# PCB_TopSchematic.net
KiCad netlist of a schematic drawn in Altium Designer
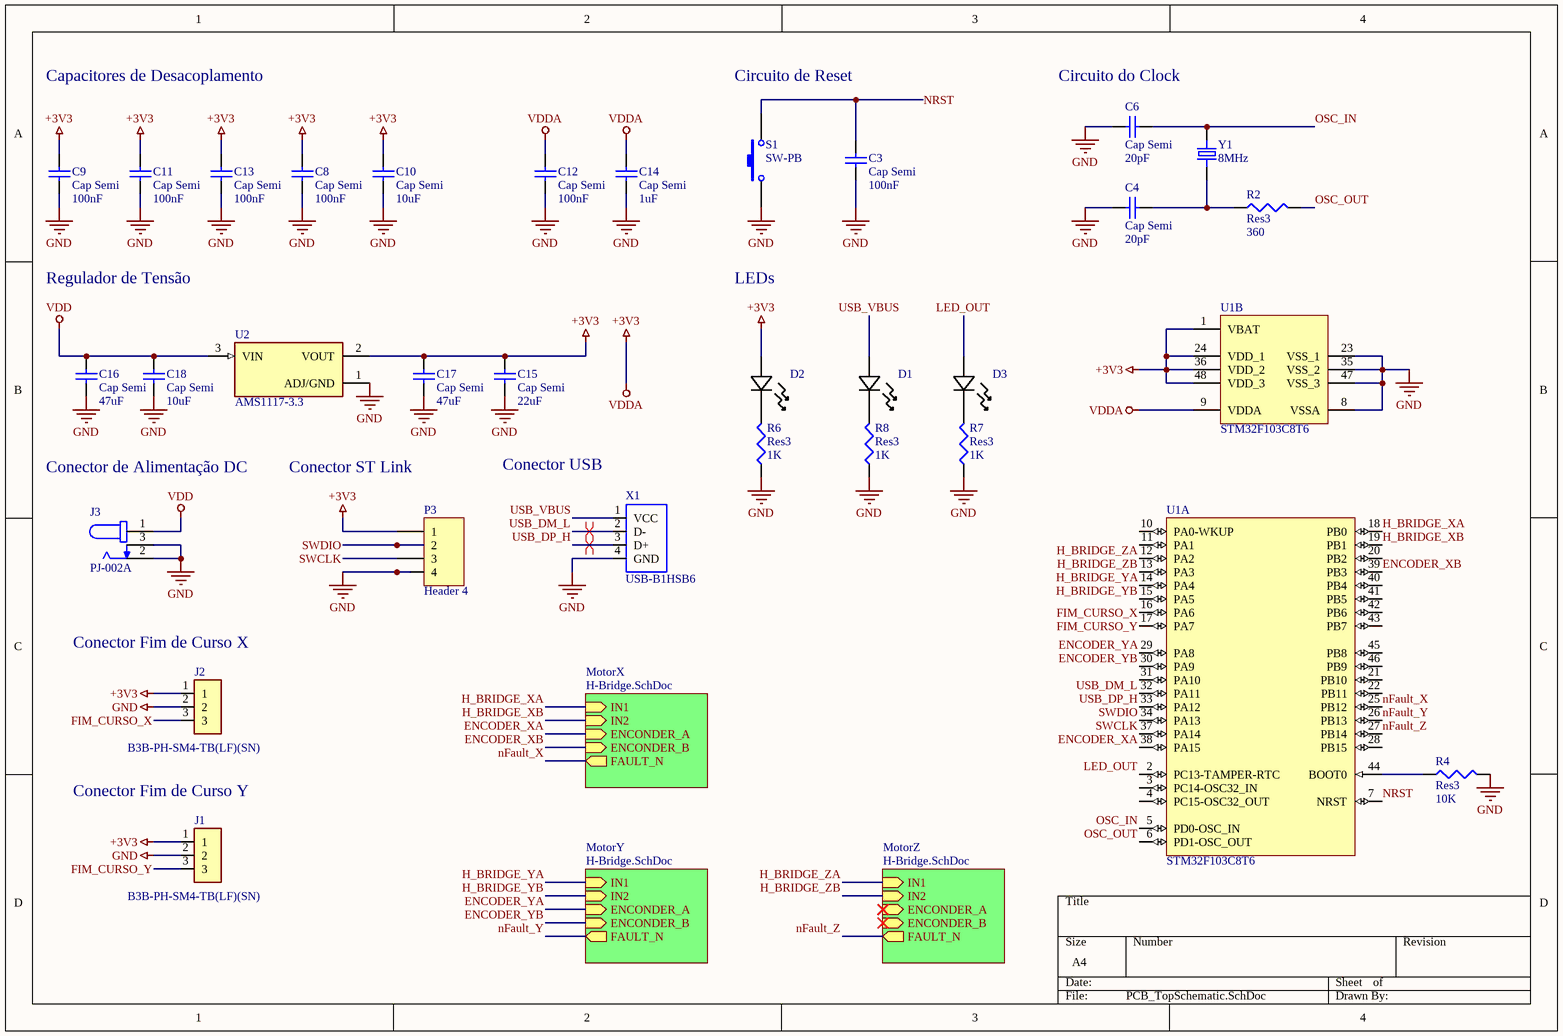
[diagram p0: PCB_TopSchematic.SchDoc]

(export (version "E")
  (design (tool "Eeschema 10.0.6"))
  (components
    (comp (ref "C3")
      (value "Cap Semi")
      (footprint "1608[0603]")
      (description "Capacitor (Semiconductor SIM Model)")
      (fields (field (name "ALTIUM_VALUE") "100nF") (field (name "PUBLISHER") "Altium Limited"))
      (libsource (lib "Miscellaneous Devices") (part "Cap Semi"))
    )
    (comp (ref "C4")
      (value "Cap Semi")
      (footprint "1608[0603]")
      (description "Capacitor (Semiconductor SIM Model)")
      (fields (field (name "ALTIUM_VALUE") "20pF") (field (name "PUBLISHER") "Altium Limited"))
      (libsource (lib "Miscellaneous Devices") (part "Cap Semi"))
    )
    (comp (ref "C6")
      (value "Cap Semi")
      (footprint "1608[0603]")
      (description "Capacitor (Semiconductor SIM Model)")
      (fields (field (name "ALTIUM_VALUE") "20pF") (field (name "PUBLISHER") "Altium Limited"))
      (libsource (lib "Miscellaneous Devices") (part "Cap Semi"))
    )
    (comp (ref "C8")
      (value "Cap Semi")
      (footprint "1608[0603]")
      (description "Capacitor (Semiconductor SIM Model)")
      (fields (field (name "ALTIUM_VALUE") "100nF") (field (name "PUBLISHER") "Altium Limited"))
      (libsource (lib "Miscellaneous Devices") (part "Cap Semi"))
    )
    (comp (ref "C9")
      (value "Cap Semi")
      (footprint "1608[0603]")
      (description "Capacitor (Semiconductor SIM Model)")
      (fields (field (name "ALTIUM_VALUE") "100nF") (field (name "PUBLISHER") "Altium Limited"))
      (libsource (lib "Miscellaneous Devices") (part "Cap Semi"))
    )
    (comp (ref "C10")
      (value "Cap Semi")
      (footprint "1608[0603]")
      (description "Capacitor (Semiconductor SIM Model)")
      (fields (field (name "ALTIUM_VALUE") "10uF") (field (name "PUBLISHER") "Altium Limited"))
      (libsource (lib "Miscellaneous Devices") (part "Cap Semi"))
    )
    (comp (ref "C11")
      (value "Cap Semi")
      (footprint "1608[0603]")
      (description "Capacitor (Semiconductor SIM Model)")
      (fields (field (name "ALTIUM_VALUE") "100nF") (field (name "PUBLISHER") "Altium Limited"))
      (libsource (lib "Miscellaneous Devices") (part "Cap Semi"))
    )
    (comp (ref "C12")
      (value "Cap Semi")
      (footprint "1608[0603]")
      (description "Capacitor (Semiconductor SIM Model)")
      (fields (field (name "ALTIUM_VALUE") "100nF") (field (name "PUBLISHER") "Altium Limited"))
      (libsource (lib "Miscellaneous Devices") (part "Cap Semi"))
    )
    (comp (ref "C13")
      (value "Cap Semi")
      (footprint "1608[0603]")
      (description "Capacitor (Semiconductor SIM Model)")
      (fields (field (name "ALTIUM_VALUE") "100nF") (field (name "PUBLISHER") "Altium Limited"))
      (libsource (lib "Miscellaneous Devices") (part "Cap Semi"))
    )
    (comp (ref "C14")
      (value "Cap Semi")
      (footprint "1608[0603]")
      (description "Capacitor (Semiconductor SIM Model)")
      (fields (field (name "ALTIUM_VALUE") "1uF") (field (name "PUBLISHER") "Altium Limited"))
      (libsource (lib "Miscellaneous Devices") (part "Cap Semi"))
    )
    (comp (ref "C15")
      (value "Cap Semi")
      (footprint "1608[0603]")
      (description "Capacitor (Semiconductor SIM Model)")
      (fields (field (name "ALTIUM_VALUE") "22uF") (field (name "PUBLISHER") "Altium Limited"))
      (libsource (lib "Miscellaneous Devices") (part "Cap Semi"))
    )
    (comp (ref "C16")
      (value "Cap Semi")
      (footprint "1608[0603]")
      (description "Capacitor (Semiconductor SIM Model)")
      (fields (field (name "ALTIUM_VALUE") "47uF") (field (name "PUBLISHER") "Altium Limited"))
      (libsource (lib "Miscellaneous Devices") (part "Cap Semi"))
    )
    (comp (ref "C17")
      (value "Cap Semi")
      (footprint "1608[0603]")
      (description "Capacitor (Semiconductor SIM Model)")
      (fields (field (name "ALTIUM_VALUE") "47uF") (field (name "PUBLISHER") "Altium Limited"))
      (libsource (lib "Miscellaneous Devices") (part "Cap Semi"))
    )
    (comp (ref "C18")
      (value "Cap Semi")
      (footprint "1608[0603]")
      (description "Capacitor (Semiconductor SIM Model)")
      (fields (field (name "ALTIUM_VALUE") "10uF") (field (name "PUBLISHER") "Altium Limited"))
      (libsource (lib "Miscellaneous Devices") (part "Cap Semi"))
    )
    (comp (ref "D1")
      (value "SML-E12M8WT86")
      (footprint "LED_SMLD12_ROM")
      (description "No Description Available")
      (fields (field (name "COPYRIGHT") "Copyright (C) 2018 Accelerated Designs. All rights reserved"))
      (libsource (lib "2020-07-03_21-25-34") (part "SML-E12M8WT86"))
    )
    (comp (ref "D2")
      (value "SML-E12M8WT86")
      (footprint "LED_SMLD12_ROM")
      (description "No Description Available")
      (fields (field (name "COPYRIGHT") "Copyright (C) 2018 Accelerated Designs. All rights reserved"))
      (libsource (lib "2020-07-03_21-25-34") (part "SML-E12M8WT86"))
    )
    (comp (ref "D3")
      (value "SML-E12M8WT86")
      (footprint "LED_SMLD12_ROM")
      (description "No Description Available")
      (fields (field (name "COPYRIGHT") "Copyright (C) 2018 Accelerated Designs. All rights reserved"))
      (libsource (lib "2020-07-03_21-25-34") (part "SML-E12M8WT86"))
    )
    (comp (ref "J1")
      (value "B3B-PH-SM4-TB(LF)(SN)")
      (footprint "JST_B3B-PH-SM4-TB(LF)(SN)")
      (description "Connector Header Surface Mount 3 position 0.079 _2.00mm_")
      (fields (field (name "MF") "JST Sales") (field (name "DIGI-KEY_PART_NUMBER") "455-1735-1-ND"))
      (libsource (lib "B3B-PH-SM4-TB_LF__SN_") (part "B3B-PH-SM4-TB(LF)(SN)"))
    )
    (comp (ref "J2")
      (value "B3B-PH-SM4-TB(LF)(SN)")
      (footprint "JST_B3B-PH-SM4-TB(LF)(SN)")
      (description "Connector Header Surface Mount 3 position 0.079 _2.00mm_")
      (fields (field (name "MF") "JST Sales") (field (name "DIGI-KEY_PART_NUMBER") "455-1735-1-ND"))
      (libsource (lib "B3B-PH-SM4-TB_LF__SN_") (part "B3B-PH-SM4-TB(LF)(SN)"))
    )
    (comp (ref "J3")
      (value "PJ-002A")
      (footprint "CUI_PJ-002A")
      (description "2,0 x 6,5 mm, 2,5 A, Yatay, A莽谋k Delik, Dc G眉莽 Jak谋 Konnekt枚r眉")
      (fields (field (name "MF") "CUI Devices"))
      (libsource (lib "PJ-002A") (part "PJ-002A"))
    )
    (comp (ref "P3")
      (value "Header 4")
      (footprint "HDR1X4")
      (description "Header, 4-Pin")
      (fields (field (name "PUBLISHER") "Altium Limited"))
      (libsource (lib "Miscellaneous Connectors") (part "Header 4"))
    )
    (comp (ref "R2")
      (value "Res3")
      (footprint "RESC1607X60N")
      (description "Resistor")
      (fields (field (name "ALTIUM_VALUE") "360") (field (name "PUBLISHER") "Altium Limited"))
      (libsource (lib "Miscellaneous Devices") (part "Res3"))
    )
    (comp (ref "R4")
      (value "Res3")
      (footprint "RESC1607X60N")
      (description "Resistor")
      (fields (field (name "ALTIUM_VALUE") "10K") (field (name "PUBLISHER") "Altium Limited"))
      (libsource (lib "Miscellaneous Devices") (part "Res3"))
    )
    (comp (ref "R6")
      (value "Res3")
      (footprint "RESC1607X60N")
      (description "Resistor")
      (fields (field (name "ALTIUM_VALUE") "1K") (field (name "PUBLISHER") "Altium Limited"))
      (libsource (lib "Miscellaneous Devices") (part "Res3"))
    )
    (comp (ref "R7")
      (value "Res3")
      (footprint "RESC1607X60N")
      (description "Resistor")
      (fields (field (name "ALTIUM_VALUE") "1K") (field (name "PUBLISHER") "Altium Limited"))
      (libsource (lib "Miscellaneous Devices") (part "Res3"))
    )
    (comp (ref "R8")
      (value "Res3")
      (footprint "RESC1607X60N")
      (description "Resistor")
      (fields (field (name "ALTIUM_VALUE") "1K") (field (name "PUBLISHER") "Altium Limited"))
      (libsource (lib "Miscellaneous Devices") (part "Res3"))
    )
    (comp (ref "S1")
      (value "SW-PB")
      (footprint "SW_B3FS-1010P")
      (description "Switch")
      (fields (field (name "PUBLISHER") "Altium Limited"))
      (libsource (lib "Miscellaneous Devices") (part "SW-PB"))
    )
    (comp (ref "U1")
      (value "STM32F103C8T6")
      (footprint "STM-LQFP48_N")
      (libsource (lib "STMicroelectronics STM32 F1") (part "STM32F103C8T6"))
    )
    (comp (ref "U2")
      (value "AMS1117-3.3")
      (footprint "SOT229P700X180-4N")
      (description "Sot223/Pkg 1-Amp 3.3-Volt Low Drop Out Voltage Regulatator")
      (fields (field (name "MF") "Advanced Monolithic Systems"))
      (libsource (lib "AMS1117-3.3") (part "AMS1117-3.3"))
    )
    (comp (ref "X1")
      (value "USB-B1HSB6")
      (footprint "OST_USB-B1HSB6")
      (description "USB-B _USB TYPE-B_ Receptacle Connector 4 Position Through Hole, Right Angle")
      (fields (field (name "DIGI-KEY_PART_NUMBER") "ED2983-ND") (field (name "MF") "On Shore"))
      (libsource (lib "USB-B1HSB6") (part "USB-B1HSB6"))
    )
    (comp (ref "Y1")
      (value "8MHz")
      (footprint "XTAL_ECS-80-20-5PX-TR")
      (description "8MHz Â±30ppm Crystal 20pF 60 Ohms HC-49/US")
      (fields (field (name "MP") "ECS-80-20-5PX-TR") (field (name "DIGI-KEY_PART_NUMBER") "XC2076CT-ND"))
      (libsource (lib "ECS-80-20-5PX-TR") (part "ECS-80-20-5PX-TR"))
    )
  )
  (nets
    (net (code "1") (name "+3V3") (class "Default")
      (node (ref "C10") (pin "2") (pinfunction "2_2") (pintype "passive"))
      (node (ref "C11") (pin "2") (pinfunction "2_2") (pintype "passive"))
      (node (ref "C12") (pin "2") (pinfunction "2_2") (pintype "passive"))
      (node (ref "C13") (pin "2") (pinfunction "2_2") (pintype "passive"))
      (node (ref "C14") (pin "2") (pinfunction "2_2") (pintype "passive"))
      (node (ref "C15") (pin "2") (pinfunction "2_2") (pintype "passive"))
      (node (ref "C17") (pin "2") (pinfunction "2_2") (pintype "passive"))
      (node (ref "C8") (pin "2") (pinfunction "2_2") (pintype "passive"))
      (node (ref "C9") (pin "2") (pinfunction "2_2") (pintype "passive"))
      (node (ref "D2") (pin "2") (pinfunction "2_2") (pintype "passive"))
      (node (ref "J1") (pin "1") (pinfunction "1_1") (pintype "passive"))
      (node (ref "J2") (pin "1") (pinfunction "1_1") (pintype "passive"))
      (node (ref "P3") (pin "1") (pinfunction "1_1") (pintype "passive"))
      (node (ref "U1") (pin "1") (pinfunction "VBAT_1") (pintype "power_in"))
      (node (ref "U1") (pin "24") (pinfunction "VDD_1_24") (pintype "power_in"))
      (node (ref "U1") (pin "36") (pinfunction "VDD_2_36") (pintype "power_in"))
      (node (ref "U1") (pin "48") (pinfunction "VDD_3_48") (pintype "power_in"))
      (node (ref "U1") (pin "9") (pinfunction "VDDA_9") (pintype "power_in"))
      (node (ref "U2") (pin "2") (pinfunction "VOUT_2") (pintype "passive"))
    )
    (net (code "2") (name "/ENCODER_XA") (class "Default")
      (node (ref "U1") (pin "38") (pinfunction "PA15_38") (pintype "bidirectional"))
    )
    (net (code "3") (name "/ENCODER_XB") (class "Default")
      (node (ref "U1") (pin "39") (pinfunction "PB3_39") (pintype "bidirectional"))
    )
    (net (code "4") (name "/ENCODER_YA") (class "Default")
      (node (ref "U1") (pin "29") (pinfunction "PA8_29") (pintype "bidirectional"))
    )
    (net (code "5") (name "/ENCODER_YB") (class "Default")
      (node (ref "U1") (pin "30") (pinfunction "PA9_30") (pintype "bidirectional"))
    )
    (net (code "8") (name "/FIM_CURSO_X") (class "Default")
      (node (ref "J2") (pin "3") (pinfunction "3_3") (pintype "passive"))
      (node (ref "U1") (pin "16") (pinfunction "PA6_16") (pintype "bidirectional"))
    )
    (net (code "9") (name "/FIM_CURSO_Y") (class "Default")
      (node (ref "J1") (pin "3") (pinfunction "3_3") (pintype "passive"))
      (node (ref "U1") (pin "17") (pinfunction "PA7_17") (pintype "bidirectional"))
    )
    (net (code "10") (name "/H_BRIDGE_XA") (class "Default")
      (node (ref "U1") (pin "18") (pinfunction "PB0_18") (pintype "bidirectional"))
    )
    (net (code "11") (name "/H_BRIDGE_XB") (class "Default")
      (node (ref "U1") (pin "19") (pinfunction "PB1_19") (pintype "bidirectional"))
    )
    (net (code "12") (name "/H_BRIDGE_YA") (class "Default")
      (node (ref "U1") (pin "14") (pinfunction "PA4_14") (pintype "bidirectional"))
    )
    (net (code "13") (name "/H_BRIDGE_YB") (class "Default")
      (node (ref "U1") (pin "15") (pinfunction "PA5_15") (pintype "bidirectional"))
    )
    (net (code "14") (name "/H_BRIDGE_ZA") (class "Default")
      (node (ref "U1") (pin "12") (pinfunction "PA2_12") (pintype "bidirectional"))
    )
    (net (code "15") (name "/H_BRIDGE_ZB") (class "Default")
      (node (ref "U1") (pin "13") (pinfunction "PA3_13") (pintype "bidirectional"))
    )
    (net (code "16") (name "/LED_OUT") (class "Default")
      (node (ref "D3") (pin "2") (pinfunction "2_2") (pintype "passive"))
      (node (ref "U1") (pin "2") (pinfunction "PC13-TAMPER-RTC_2") (pintype "bidirectional"))
    )
    (net (code "17") (name "/NRST") (class "Default")
      (node (ref "C3") (pin "2") (pinfunction "2_2") (pintype "passive"))
      (node (ref "S1") (pin "2") (pinfunction "2_2") (pintype "passive"))
      (node (ref "U1") (pin "7") (pinfunction "NRST_7") (pintype "bidirectional"))
    )
    (net (code "18") (name "/OSC_IN") (class "Default")
      (node (ref "C6") (pin "1") (pinfunction "1_1") (pintype "passive"))
      (node (ref "U1") (pin "5") (pinfunction "PD0-OSC_IN_5") (pintype "bidirectional"))
      (node (ref "Y1") (pin "1") (pinfunction "1_1") (pintype "passive"))
    )
    (net (code "19") (name "/OSC_OUT") (class "Default")
      (node (ref "R2") (pin "2") (pinfunction "2_2") (pintype "passive"))
      (node (ref "U1") (pin "6") (pinfunction "PD1-OSC_OUT_6") (pintype "bidirectional"))
    )
    (net (code "20") (name "/SWCLK") (class "Default")
      (node (ref "P3") (pin "3") (pinfunction "3_3") (pintype "passive"))
      (node (ref "U1") (pin "37") (pinfunction "PA14_37") (pintype "bidirectional"))
    )
    (net (code "21") (name "/SWDIO") (class "Default")
      (node (ref "P3") (pin "2") (pinfunction "2_2") (pintype "passive"))
      (node (ref "U1") (pin "34") (pinfunction "PA13_34") (pintype "bidirectional"))
    )
    (net (code "22") (name "/USB_DM_L") (class "Default")
      (node (ref "U1") (pin "32") (pinfunction "PA11_32") (pintype "bidirectional"))
      (node (ref "X1") (pin "2") (pinfunction "D-_2") (pintype "bidirectional"))
    )
    (net (code "23") (name "/USB_DP_H") (class "Default")
      (node (ref "U1") (pin "33") (pinfunction "PA12_33") (pintype "bidirectional"))
      (node (ref "X1") (pin "3") (pinfunction "D+_3") (pintype "bidirectional"))
    )
    (net (code "24") (name "/USB_VBUS") (class "Default")
      (node (ref "D1") (pin "2") (pinfunction "2_2") (pintype "passive"))
      (node (ref "X1") (pin "1") (pinfunction "VCC_1") (pintype "power_in"))
    )
    (net (code "25") (name "/nFault_X") (class "Default")
      (node (ref "U1") (pin "25") (pinfunction "PB12_25") (pintype "bidirectional"))
    )
    (net (code "26") (name "/nFault_Y") (class "Default")
      (node (ref "U1") (pin "26") (pinfunction "PB13_26") (pintype "bidirectional"))
    )
    (net (code "27") (name "/nFault_Z") (class "Default")
      (node (ref "U1") (pin "27") (pinfunction "PB14_27") (pintype "bidirectional"))
    )
    (net (code "28") (name "GND") (class "Default")
      (node (ref "C10") (pin "1") (pinfunction "1_1") (pintype "passive"))
      (node (ref "C11") (pin "1") (pinfunction "1_1") (pintype "passive"))
      (node (ref "C12") (pin "1") (pinfunction "1_1") (pintype "passive"))
      (node (ref "C13") (pin "1") (pinfunction "1_1") (pintype "passive"))
      (node (ref "C14") (pin "1") (pinfunction "1_1") (pintype "passive"))
      (node (ref "C15") (pin "1") (pinfunction "1_1") (pintype "passive"))
      (node (ref "C16") (pin "1") (pinfunction "1_1") (pintype "passive"))
      (node (ref "C17") (pin "1") (pinfunction "1_1") (pintype "passive"))
      (node (ref "C18") (pin "1") (pinfunction "1_1") (pintype "passive"))
      (node (ref "C3") (pin "1") (pinfunction "1_1") (pintype "passive"))
      (node (ref "C4") (pin "2") (pinfunction "2_2") (pintype "passive"))
      (node (ref "C6") (pin "2") (pinfunction "2_2") (pintype "passive"))
      (node (ref "C8") (pin "1") (pinfunction "1_1") (pintype "passive"))
      (node (ref "C9") (pin "1") (pinfunction "1_1") (pintype "passive"))
      (node (ref "J1") (pin "2") (pinfunction "2_2") (pintype "passive"))
      (node (ref "J2") (pin "2") (pinfunction "2_2") (pintype "passive"))
      (node (ref "J3") (pin "2") (pinfunction "2_2") (pintype "passive"))
      (node (ref "J3") (pin "3") (pinfunction "3_3") (pintype "passive"))
      (node (ref "P3") (pin "4") (pinfunction "4_4") (pintype "passive"))
      (node (ref "R4") (pin "2") (pinfunction "2_2") (pintype "passive"))
      (node (ref "R6") (pin "1") (pinfunction "1_1") (pintype "passive"))
      (node (ref "R7") (pin "1") (pinfunction "1_1") (pintype "passive"))
      (node (ref "R8") (pin "1") (pinfunction "1_1") (pintype "passive"))
      (node (ref "S1") (pin "1") (pinfunction "1_1") (pintype "passive"))
      (node (ref "U1") (pin "23") (pinfunction "VSS_1_23") (pintype "power_in"))
      (node (ref "U1") (pin "35") (pinfunction "VSS_2_35") (pintype "power_in"))
      (node (ref "U1") (pin "47") (pinfunction "VSS_3_47") (pintype "power_in"))
      (node (ref "U1") (pin "8") (pinfunction "VSSA_8") (pintype "power_in"))
      (node (ref "U2") (pin "1") (pinfunction "ADJ/GND_1") (pintype "power_in"))
      (node (ref "X1") (pin "4") (pinfunction "GND_4") (pintype "power_in"))
    )
    (net (code "29") (name "Net-(C4-Pad1)") (class "Default")
      (node (ref "C4") (pin "1") (pinfunction "1_1") (pintype "passive"))
      (node (ref "R2") (pin "1") (pinfunction "1_1") (pintype "passive"))
      (node (ref "Y1") (pin "2") (pinfunction "2_2") (pintype "passive"))
    )
    (net (code "30") (name "Net-(D1-Pad1)") (class "Default")
      (node (ref "D1") (pin "1") (pinfunction "1_1") (pintype "passive"))
      (node (ref "R8") (pin "2") (pinfunction "2_2") (pintype "passive"))
    )
    (net (code "31") (name "Net-(D2-Pad1)") (class "Default")
      (node (ref "D2") (pin "1") (pinfunction "1_1") (pintype "passive"))
      (node (ref "R6") (pin "2") (pinfunction "2_2") (pintype "passive"))
    )
    (net (code "32") (name "Net-(D3-Pad1)") (class "Default")
      (node (ref "D3") (pin "1") (pinfunction "1_1") (pintype "passive"))
      (node (ref "R7") (pin "2") (pinfunction "2_2") (pintype "passive"))
    )
    (net (code "33") (name "Net-(U1A-BOOT0)") (class "Default")
      (node (ref "R4") (pin "1") (pinfunction "1_1") (pintype "passive"))
      (node (ref "U1") (pin "44") (pinfunction "BOOT0_44") (pintype "input"))
    )
    (net (code "34") (name "VDD") (class "Default")
      (node (ref "C16") (pin "2") (pinfunction "2_2") (pintype "passive"))
      (node (ref "C18") (pin "2") (pinfunction "2_2") (pintype "passive"))
      (node (ref "J3") (pin "1") (pinfunction "1_1") (pintype "passive"))
      (node (ref "U2") (pin "3") (pinfunction "VIN_3") (pintype "input"))
    )
    (net (code "35") (name "unconnected-(U1A-PA0-WKUP-Pad10)") (class "Default")
      (node (ref "U1") (pin "10") (pinfunction "PA0-WKUP_10") (pintype "bidirectional"))
    )
    (net (code "36") (name "unconnected-(U1A-PA1-Pad11)") (class "Default")
      (node (ref "U1") (pin "11") (pinfunction "PA1_11") (pintype "bidirectional"))
    )
    (net (code "37") (name "unconnected-(U1A-PA10-Pad31)") (class "Default")
      (node (ref "U1") (pin "31") (pinfunction "PA10_31") (pintype "bidirectional"))
    )
    (net (code "38") (name "unconnected-(U1A-PB2-Pad20)") (class "Default")
      (node (ref "U1") (pin "20") (pinfunction "PB2_20") (pintype "bidirectional"))
    )
    (net (code "39") (name "unconnected-(U1A-PB4-Pad40)") (class "Default")
      (node (ref "U1") (pin "40") (pinfunction "PB4_40") (pintype "bidirectional"))
    )
    (net (code "40") (name "unconnected-(U1A-PB5-Pad41)") (class "Default")
      (node (ref "U1") (pin "41") (pinfunction "PB5_41") (pintype "bidirectional"))
    )
    (net (code "41") (name "unconnected-(U1A-PB6-Pad42)") (class "Default")
      (node (ref "U1") (pin "42") (pinfunction "PB6_42") (pintype "bidirectional"))
    )
    (net (code "42") (name "unconnected-(U1A-PB7-Pad43)") (class "Default")
      (node (ref "U1") (pin "43") (pinfunction "PB7_43") (pintype "bidirectional"))
    )
    (net (code "43") (name "unconnected-(U1A-PB8-Pad45)") (class "Default")
      (node (ref "U1") (pin "45") (pinfunction "PB8_45") (pintype "bidirectional"))
    )
    (net (code "44") (name "unconnected-(U1A-PB9-Pad46)") (class "Default")
      (node (ref "U1") (pin "46") (pinfunction "PB9_46") (pintype "bidirectional"))
    )
    (net (code "45") (name "unconnected-(U1A-PB10-Pad21)") (class "Default")
      (node (ref "U1") (pin "21") (pinfunction "PB10_21") (pintype "bidirectional"))
    )
    (net (code "46") (name "unconnected-(U1A-PB11-Pad22)") (class "Default")
      (node (ref "U1") (pin "22") (pinfunction "PB11_22") (pintype "bidirectional"))
    )
    (net (code "47") (name "unconnected-(U1A-PB15-Pad28)") (class "Default")
      (node (ref "U1") (pin "28") (pinfunction "PB15_28") (pintype "bidirectional"))
    )
    (net (code "48") (name "unconnected-(U1A-PC14-OSC32_IN-Pad3)") (class "Default")
      (node (ref "U1") (pin "3") (pinfunction "PC14-OSC32_IN_3") (pintype "bidirectional"))
    )
    (net (code "49") (name "unconnected-(U1A-PC15-OSC32_OUT-Pad4)") (class "Default")
      (node (ref "U1") (pin "4") (pinfunction "PC15-OSC32_OUT_4") (pintype "bidirectional"))
    )
  )
)
